# NCS_Wireless_Bed_Unit_Power_Supply.net
KiCad netlist of a schematic drawn in Altium Designer
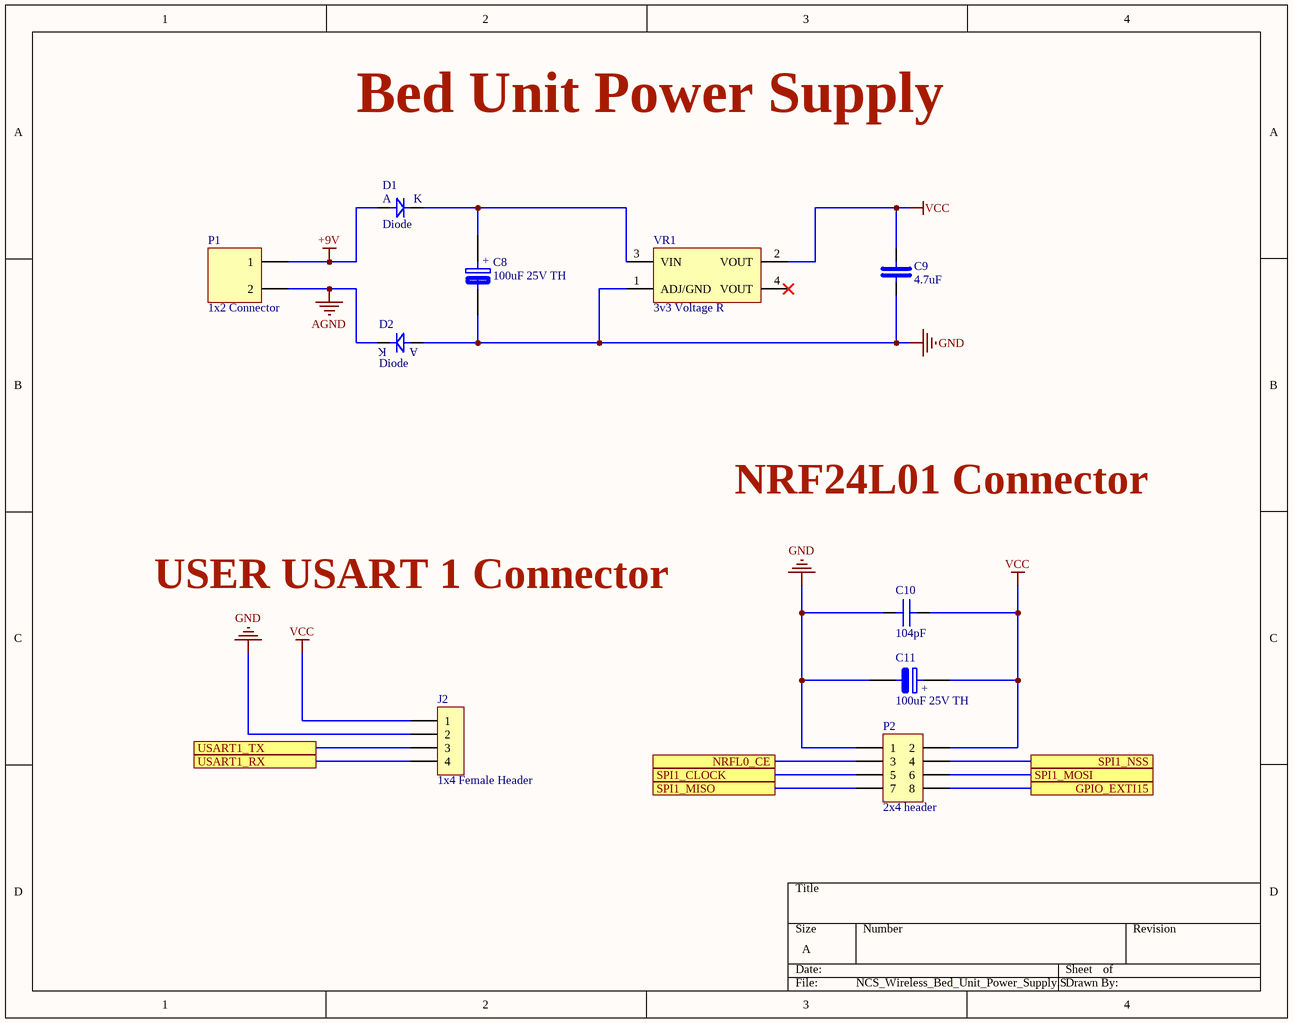
[diagram p0: NCS_Wireless_Bed_Unit_Power_Supply.SchDoc]

(export (version "E")
  (design (tool "Eeschema 10.0.6"))
  (components
    (comp (ref "C8")
      (value "100uF 25V TH")
      (footprint "100uF 25V TH")
      (description "WCAP-ATG8 Aluminum Electrolytic Capacitors")
      (fields
        (field (name "MANUFACTURER") "Wurth Electronics")
        (field (name "MANUFACTURER PART NUMBER") "860010473007")
      )
      (libsource (lib "schlib") (part "860010473007"))
    )
    (comp (ref "C9")
      (value "4.7uF")
      (footprint "C0805C209D3HACTU_2pF")
      (description "Multilayer Ceramic Capacitor, 4.7 uF, 25 V, ï¿½ 10%, X5R, 0805 [2012 Metric]")
      (fields
        (field (name "MANUFACTURER") "KEMET")
        (field (name "MANUFACTURER PART NUMBER") "C0805C475K3PACTU")
      )
      (libsource (lib "schlib") (part "C0805C475K3PACTU"))
    )
    (comp (ref "C10")
      (value "104pF")
      (footprint "C0805C471K3RACTU_470pF")
      (description "Capacitor, Ceramic, 470pF, 25VDC, 10-% Tol, 10+% Tol, X7R-TC Code, -15, 15%-TC RoHS Compliant: Yes")
      (fields
        (field (name "MANUFACTURER") "KEMET")
        (field (name "MANUFACTURER PART NUMBER") "C0805C471K3RACTU")
      )
      (libsource (lib "schlib") (part "C0805C471K3RACTU"))
    )
    (comp (ref "C11")
      (value "100uF 25V TH")
      (footprint "100uF 25V TH")
      (description "WCAP-ATG8 Aluminum Electrolytic Capacitors")
      (fields
        (field (name "MANUFACTURER") "Wurth Electronics")
        (field (name "MANUFACTURER PART NUMBER") "860010473007")
      )
      (libsource (lib "schlib") (part "860010473007"))
    )
    (comp (ref "D1")
      (value "Diode")
      (footprint "CRS06(TE85L,Q,M)_DIODE")
      (description "Diode Schottky 20V 1A 2-Pin S-FLAT T/R / DIODE SCHOTTKY 20V 1A SFLAT")
      (fields
        (field (name "MANUFACTURER") "Toshiba")
        (field (name "MANUFACTURER PART NUMBER") "CRS06(TE85L,Q,M)")
      )
      (libsource (lib "schlib") (part "CRS06(TE85L,Q,M)"))
    )
    (comp (ref "D2")
      (value "Diode")
      (footprint "CRS06(TE85L,Q,M)_DIODE")
      (description "Diode Schottky 20V 1A 2-Pin S-FLAT T/R / DIODE SCHOTTKY 20V 1A SFLAT")
      (fields
        (field (name "MANUFACTURER") "Toshiba")
        (field (name "MANUFACTURER PART NUMBER") "CRS06(TE85L,Q,M)")
      )
      (libsource (lib "schlib") (part "CRS06(TE85L,Q,M)"))
    )
    (comp (ref "J2")
      (value "1x4 Female Header")
      (footprint "1x4 Female Header")
      (description "Female, 4 C, Straight, .100\"CC; 3.20mm Tail, No Mounting; PBT, Phos. Bronze, 105 C")
      (fields
        (field (name "MANUFACTURER") "Sullins")
        (field (name "MANUFACTURER PART NUMBER") "PPPC041LFBN-RC")
      )
      (libsource (lib "schlib") (part "PPPC041LFBN-RC"))
    )
    (comp (ref "P1")
      (value "1x2 Connector")
      (footprint "1x2 Connector")
      (description "2~24 Poles, Screw Type, Horizontal, 5.08 Pitch, 26~14 (AWG), Terminal Block Connector")
      (fields (field (name "MANUFACTURER") "CUI") (field (name "MANUFACTURER PART NUMBER") "TB006-508-02BE"))
      (libsource (lib "schlib") (part "TB006-508-02BE"))
    )
    (comp (ref "P2")
      (value "2x4 header")
      (footprint "2x4 header")
      (description "Header Connector, Pcb Mnt, 8 Contacts, Skt, 0.1 Pitch, Pc Tail Terminal, Locking")
      (fields
        (field (name "MANUFACTURER") "Sullins")
        (field (name "MANUFACTURER PART NUMBER") "PPTC042LFBN-RC")
      )
      (libsource (lib "schlib") (part "PPTC042LFBN-RC"))
    )
    (comp (ref "VR1")
      (value "3v3 Voltage R")
      (footprint "SAMS1117-33-4N")
      (libsource (lib "NCS_Wireless_Bed_Unit") (part "AMS1117-33-3.3V"))
    )
  )
  (nets
    (net (code "1") (name "+9V") (class "Default")
      (node (ref "D1") (pin "1") (pinfunction "1_1") (pintype "passive"))
      (node (ref "P1") (pin "1") (pinfunction "1_1") (pintype "passive"))
    )
    (net (code "2") (name "/GPIO_EXTI15") (class "Default")
      (node (ref "P2") (pin "8") (pinfunction "8_8") (pintype "passive"))
    )
    (net (code "3") (name "/NRFL0_CE") (class "Default")
      (node (ref "P2") (pin "3") (pinfunction "3_3") (pintype "passive"))
    )
    (net (code "4") (name "/SPI1_CLOCK") (class "Default")
      (node (ref "P2") (pin "5") (pinfunction "5_5") (pintype "passive"))
    )
    (net (code "5") (name "/SPI1_MISO") (class "Default")
      (node (ref "P2") (pin "7") (pinfunction "7_7") (pintype "passive"))
    )
    (net (code "6") (name "/SPI1_MOSI") (class "Default")
      (node (ref "P2") (pin "6") (pinfunction "6_6") (pintype "passive"))
    )
    (net (code "7") (name "/SPI1_NSS") (class "Default")
      (node (ref "P2") (pin "4") (pinfunction "4_4") (pintype "passive"))
    )
    (net (code "8") (name "/USART1_RX") (class "Default")
      (node (ref "J2") (pin "4") (pinfunction "4_4") (pintype "passive"))
    )
    (net (code "9") (name "/USART1_TX") (class "Default")
      (node (ref "J2") (pin "3") (pinfunction "3_3") (pintype "passive"))
    )
    (net (code "10") (name "AGND") (class "Default")
      (node (ref "D2") (pin "2") (pinfunction "2_2") (pintype "passive"))
      (node (ref "P1") (pin "2") (pinfunction "2_2") (pintype "passive"))
    )
    (net (code "11") (name "GND") (class "Default")
      (node (ref "C10") (pin "1") (pinfunction "1_1") (pintype "passive"))
      (node (ref "C11") (pin "2") (pinfunction "2_2") (pintype "passive"))
      (node (ref "C8") (pin "2") (pinfunction "2_2") (pintype "passive"))
      (node (ref "C9") (pin "1") (pinfunction "1_1") (pintype "passive"))
      (node (ref "D2") (pin "1") (pinfunction "1_1") (pintype "passive"))
      (node (ref "J2") (pin "2") (pinfunction "2_2") (pintype "passive"))
      (node (ref "P2") (pin "1") (pinfunction "1_1") (pintype "passive"))
      (node (ref "VR1") (pin "1") (pinfunction "ADJ/GND_1") (pintype "passive"))
    )
    (net (code "12") (name "Net-(VR1-VIN)") (class "Default")
      (node (ref "C8") (pin "1") (pinfunction "1_1") (pintype "passive"))
      (node (ref "D1") (pin "2") (pinfunction "2_2") (pintype "passive"))
      (node (ref "VR1") (pin "3") (pinfunction "VIN_3") (pintype "passive"))
    )
    (net (code "13") (name "VCC") (class "Default")
      (node (ref "C10") (pin "2") (pinfunction "2_2") (pintype "passive"))
      (node (ref "C11") (pin "1") (pinfunction "1_1") (pintype "passive"))
      (node (ref "C9") (pin "2") (pinfunction "2_2") (pintype "passive"))
      (node (ref "J2") (pin "1") (pinfunction "1_1") (pintype "passive"))
      (node (ref "P2") (pin "2") (pinfunction "2_2") (pintype "passive"))
      (node (ref "VR1") (pin "2") (pinfunction "VOUT_2") (pintype "passive"))
    )
    (net (code "14") (name "unconnected-(VR1-VOUT-Pad4)") (class "Default")
      (node (ref "VR1") (pin "4") (pinfunction "VOUT_4") (pintype "passive+no_connect"))
    )
  )
)
